# 3_0.net
KiCad netlist of a schematic drawn in Altium Designer
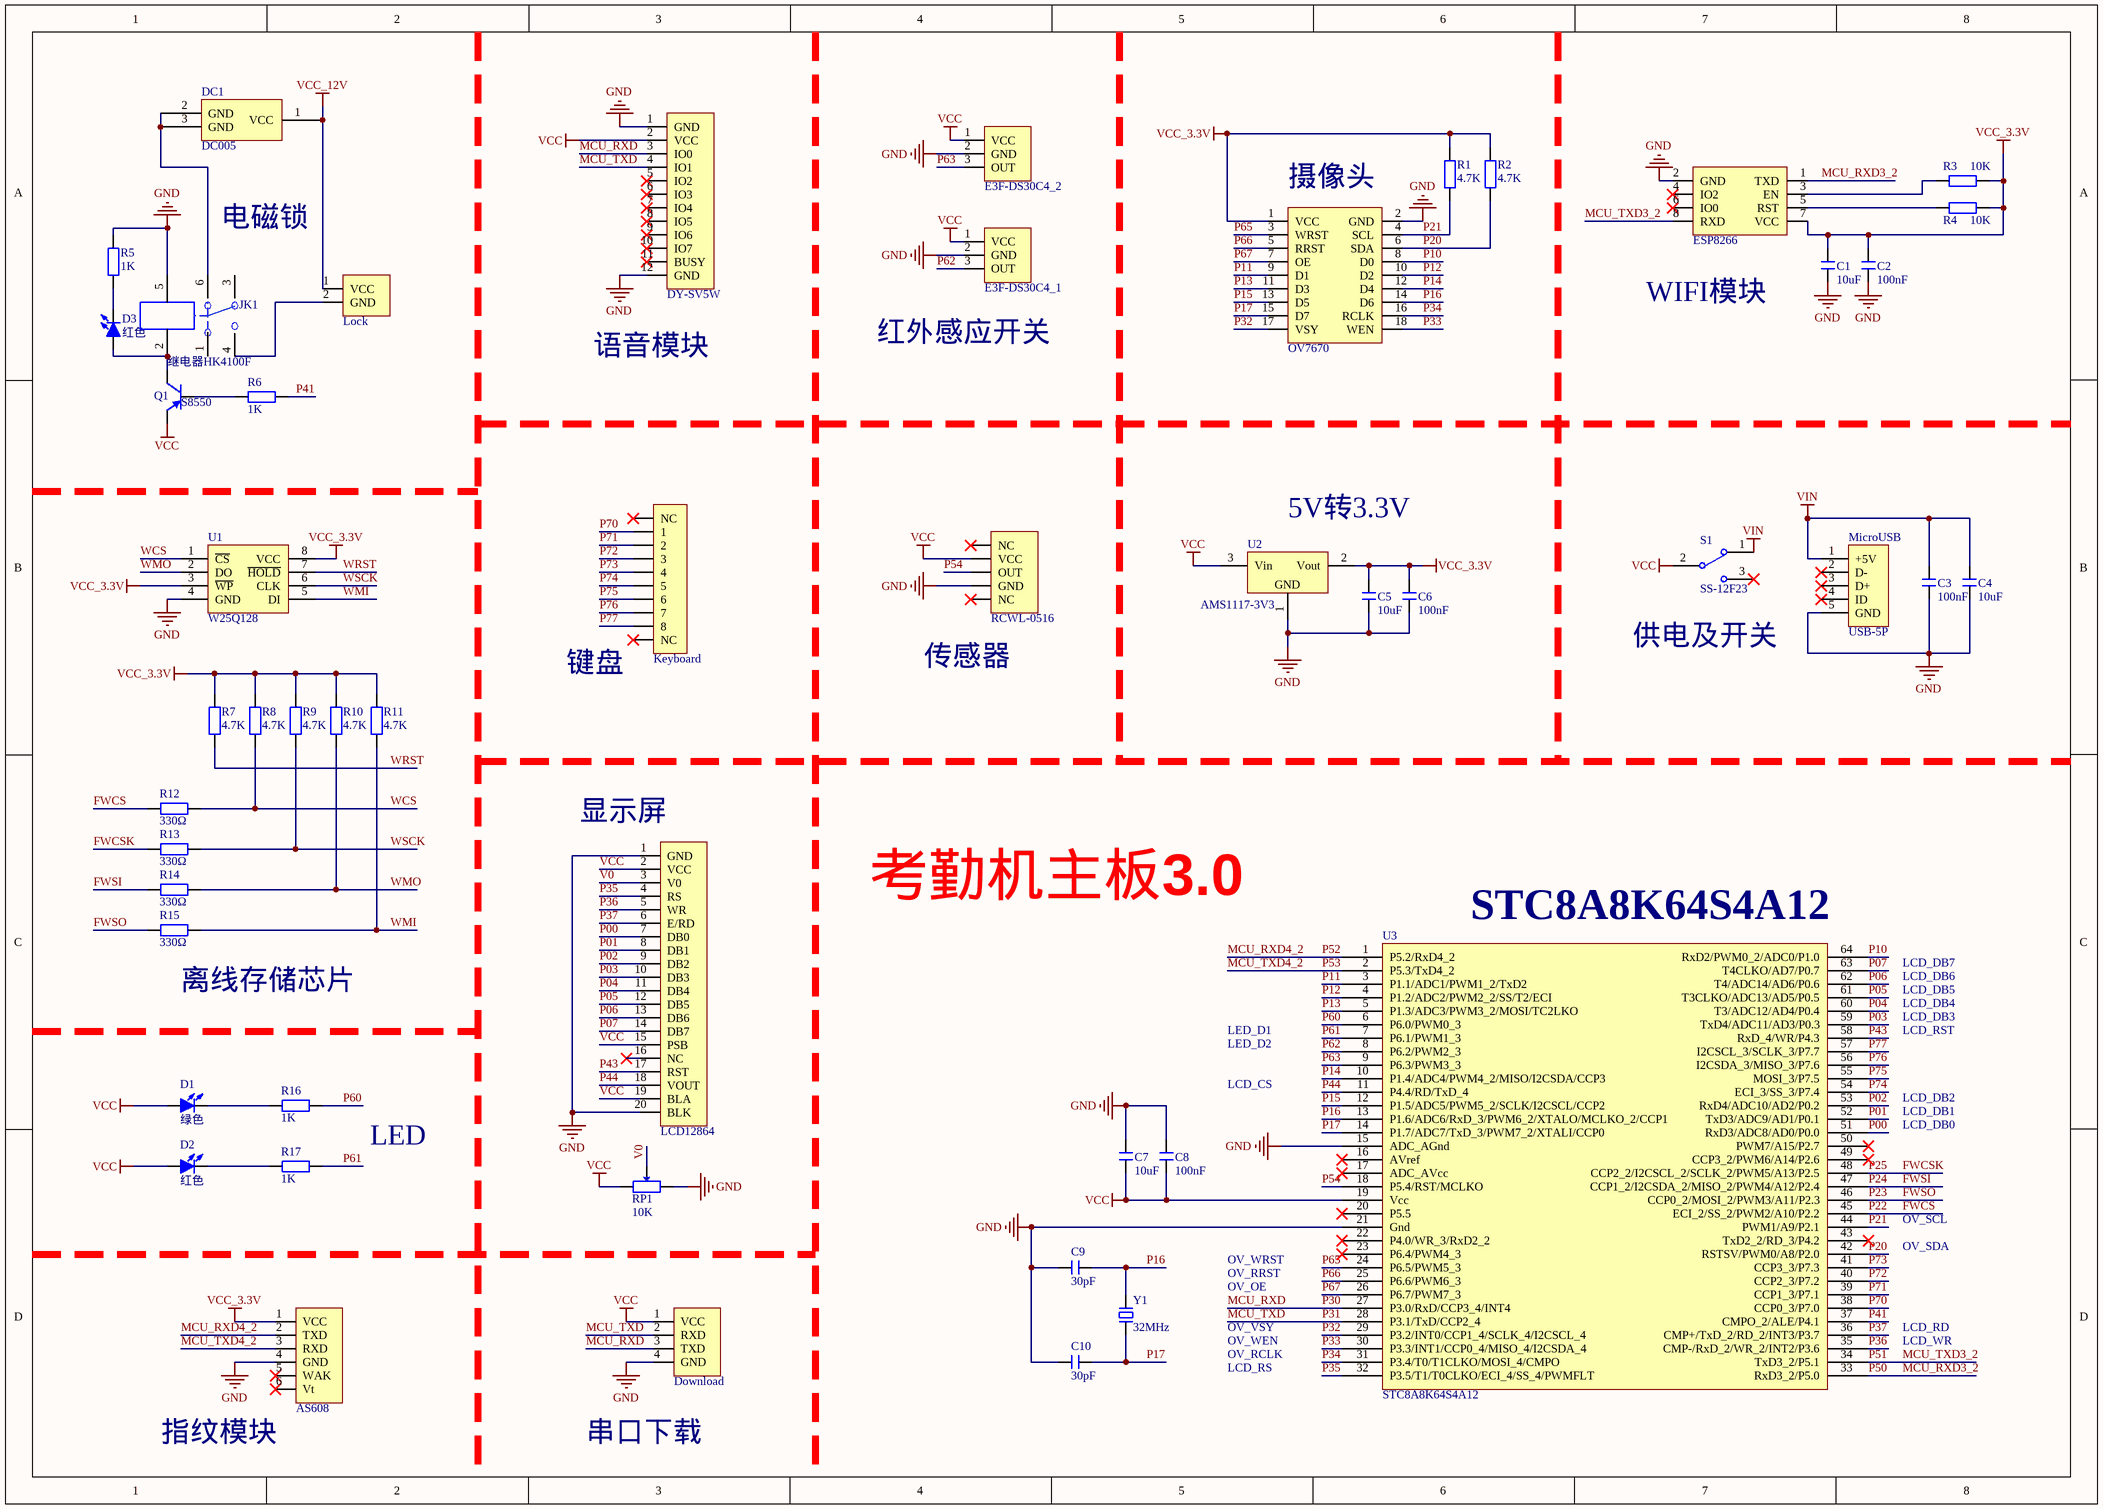
[diagram p0: 考勤机主板3.0.SchDoc]

(export (version "E")
  (design (tool "Eeschema 10.0.6"))
  (components
    (comp (ref "AS608")
      (value "HDR-1X6")
      (footprint "HDR2.54-LI-6P")
      (description "AS608")
      (fields (field (name "版权归属") "源创客"))
      (libsource (lib "考勤机主板3.0.") (part "指纹模块"))
    )
    (comp (ref "C1")
      (value "10uF")
      (footprint "C 0805_M")
      (description "无极性贴片电容")
      (fields (field (name "版权归属") "源创客"))
      (libsource (lib "考勤机主板3.0.") (part "C"))
    )
    (comp (ref "C2")
      (value "100nF")
      (footprint "C 0805_M")
      (description "无极性贴片电容")
      (fields (field (name "版权归属") "源创客"))
      (libsource (lib "考勤机主板3.0.") (part "C"))
    )
    (comp (ref "C3")
      (value "100nF")
      (footprint "C 0805_M")
      (description "无极性贴片电容")
      (fields (field (name "版权归属") "源创客"))
      (libsource (lib "考勤机主板3.0.") (part "C"))
    )
    (comp (ref "C4")
      (value "10uF")
      (footprint "C 0805_M")
      (description "无极性贴片电容")
      (fields (field (name "版权归属") "源创客"))
      (libsource (lib "考勤机主板3.0.") (part "C"))
    )
    (comp (ref "C5")
      (value "10uF")
      (footprint "C 0805_M")
      (description "无极性贴片电容")
      (fields (field (name "版权归属") "源创客"))
      (libsource (lib "考勤机主板3.0.") (part "C"))
    )
    (comp (ref "C6")
      (value "100nF")
      (footprint "C 0805_M")
      (description "无极性贴片电容")
      (fields (field (name "版权归属") "源创客"))
      (libsource (lib "考勤机主板3.0.") (part "C"))
    )
    (comp (ref "C7")
      (value "10uF")
      (footprint "C 0805_M")
      (description "无极性贴片电容")
      (fields (field (name "版权归属") "源创客"))
      (libsource (lib "考勤机主板3.0.") (part "C"))
    )
    (comp (ref "C8")
      (value "100nF")
      (footprint "C 0805_M")
      (description "无极性贴片电容")
      (fields (field (name "版权归属") "源创客"))
      (libsource (lib "考勤机主板3.0.") (part "C"))
    )
    (comp (ref "C9")
      (value "30pF")
      (footprint "C 0805_M")
      (description "无极性贴片电容")
      (fields (field (name "版权归属") "源创客"))
      (libsource (lib "考勤机主板3.0.") (part "C"))
    )
    (comp (ref "C10")
      (value "30pF")
      (footprint "C 0805_M")
      (description "无极性贴片电容")
      (fields (field (name "版权归属") "源创客"))
      (libsource (lib "考勤机主板3.0.") (part "C"))
    )
    (comp (ref "D1")
      (value "绿色")
      (footprint "LED 0805G")
      (description "贴片LED")
      (fields (field (name "版权归属") "源创客"))
      (libsource (lib "考勤机主板3.0.") (part "LED-SMD"))
    )
    (comp (ref "D2")
      (value "红色")
      (footprint "LED 0805R")
      (description "贴片LED")
      (fields (field (name "版权归属") "源创客"))
      (libsource (lib "考勤机主板3.0.") (part "LED-SMD"))
    )
    (comp (ref "D3")
      (value "红色")
      (footprint "LED 0805G")
      (description "贴片LED")
      (fields (field (name "版权归属") "源创客"))
      (libsource (lib "考勤机主板3.0.") (part "LED-SMD"))
    )
    (comp (ref "DC1") (value "DC005") (footprint "DC-005") (libsource (lib "考勤机主板3.0.") (part "DC005")))
    (comp (ref "Download")
      (value "HDR-1X4")
      (footprint "HDR2.54-LI-4P")
      (description "串口下载")
      (fields (field (name "版权归属") "源创客"))
      (libsource (lib "考勤机主板3.0.") (part "串口下载"))
    )
    (comp (ref "DY-SV5W")
      (value "HDR-1X12")
      (footprint "HDR2.54-M-LI-12P")
      (description "DY-SV5W")
      (fields (field (name "版权归属") "源创客"))
      (libsource (lib "考勤机主板3.0.") (part "语音模块"))
    )
    (comp (ref "E3F-DS30C4_1")
      (value "HDR-1X3")
      (footprint "HDR2.54-M-LI-3P")
      (description "E3F-DS30C4")
      (fields (field (name "版权归属") "源创客"))
      (libsource (lib "考勤机主板3.0.") (part "红外感应开关"))
    )
    (comp (ref "E3F-DS30C4_2")
      (value "HDR-1X3")
      (footprint "HDR2.54-M-LI-3P")
      (description "E3F-DS30C4")
      (fields (field (name "版权归属") "源创客"))
      (libsource (lib "考勤机主板3.0.") (part "红外感应开关"))
    )
    (comp (ref "ESP8266")
      (value "Header 4X2")
      (footprint "HDR2.54-LI-2x4P")
      (description "ESP8266-01")
      (fields (field (name "版权归属") "源创客"))
      (libsource (lib "考勤机主板3.0.") (part "WIFI模块"))
    )
    (comp (ref "JK1")
      (value "继电器HK4100F")
      (footprint "HK4100F - duplicate")
      (libsource (lib "元件库") (part "继电器HK4100F"))
    )
    (comp (ref "Keyboard")
      (value "HDR-1X10")
      (footprint "HDR2.54-M-LI-10P")
      (description "Keyboard")
      (fields (field (name "版权归属") "源创客"))
      (libsource (lib "考勤机主板3.0.") (part "键盘"))
    )
    (comp (ref "LCD12864")
      (value "HDR-1X20")
      (footprint "HDR2.54-M-LI-20P")
      (description "LCD12864")
      (fields (field (name "版权归属") "源创客"))
      (libsource (lib "考勤机主板3.0.") (part "显示屏"))
    )
    (comp (ref "Lock")
      (value "HDR-1X2")
      (footprint "XH2.54-WI-2P")
      (description "电磁锁")
      (fields (field (name "版权归属") "源创客"))
      (libsource (lib "考勤机主板3.0.") (part "电磁锁"))
    )
    (comp (ref "MicroUSB")
      (value "USB-5P")
      (footprint "USB")
      (description "MicroUSB")
      (fields (field (name "版权归属") "源创客"))
      (libsource (lib "考勤机主板3.0.") (part "MiceoUSB接口"))
    )
    (comp (ref "OV7670")
      (value "Header 9X2")
      (footprint "HDR2.54-LI-2x9P")
      (description "OV7670")
      (fields (field (name "版权归属") "源创客"))
      (libsource (lib "考勤机主板3.0.") (part "摄像头"))
    )
    (comp (ref "Q1")
      (value "S8550")
      (footprint "SOT23-3M")
      (description "高频放大-PNP型")
      (fields (field (name "版权归属") "源创客"))
      (libsource (lib "考勤机主板3.0.") (part "8550-SMD"))
    )
    (comp (ref "R1")
      (value "4.7K")
      (footprint "R 0805_M")
      (description "贴片电阻")
      (fields (field (name "版权归属") "源创客"))
      (libsource (lib "3.1   - 电阻-电容-电感") (part "R"))
    )
    (comp (ref "R2")
      (value "4.7K")
      (footprint "R 0805_M")
      (description "贴片电阻")
      (fields (field (name "版权归属") "源创客"))
      (libsource (lib "3.1   - 电阻-电容-电感") (part "R"))
    )
    (comp (ref "R3")
      (value "10K")
      (footprint "R 0805_M")
      (description "贴片电阻")
      (fields (field (name "版权归属") "源创客"))
      (libsource (lib "3.1   - 电阻-电容-电感") (part "R"))
    )
    (comp (ref "R4")
      (value "10K")
      (footprint "R 0805_M")
      (description "贴片电阻")
      (fields (field (name "版权归属") "源创客"))
      (libsource (lib "3.1   - 电阻-电容-电感") (part "R"))
    )
    (comp (ref "R5")
      (value "1K")
      (footprint "R 0805_M")
      (description "贴片电阻")
      (fields (field (name "版权归属") "源创客"))
      (libsource (lib "3.1   - 电阻-电容-电感") (part "R"))
    )
    (comp (ref "R6")
      (value "1K")
      (footprint "R 0805_M")
      (description "贴片电阻")
      (fields (field (name "版权归属") "源创客"))
      (libsource (lib "考勤机主板3.0.") (part "R"))
    )
    (comp (ref "R7")
      (value "4.7K")
      (footprint "R 0805_M")
      (description "贴片电阻")
      (fields (field (name "版权归属") "源创客"))
      (libsource (lib "考勤机主板3.0.") (part "R"))
    )
    (comp (ref "R8")
      (value "4.7K")
      (footprint "R 0805_M")
      (description "贴片电阻")
      (fields (field (name "版权归属") "源创客"))
      (libsource (lib "考勤机主板3.0.") (part "R"))
    )
    (comp (ref "R9")
      (value "4.7K")
      (footprint "R 0805_M")
      (description "贴片电阻")
      (fields (field (name "版权归属") "源创客"))
      (libsource (lib "考勤机主板3.0.") (part "R"))
    )
    (comp (ref "R10")
      (value "4.7K")
      (footprint "R 0805_M")
      (description "贴片电阻")
      (fields (field (name "版权归属") "源创客"))
      (libsource (lib "考勤机主板3.0.") (part "R"))
    )
    (comp (ref "R11")
      (value "4.7K")
      (footprint "R 0805_M")
      (description "贴片电阻")
      (fields (field (name "版权归属") "源创客"))
      (libsource (lib "考勤机主板3.0.") (part "R"))
    )
    (comp (ref "R12")
      (value "330Ω")
      (footprint "R 0805_M")
      (description "贴片电阻")
      (fields (field (name "版权归属") "源创客"))
      (libsource (lib "考勤机主板3.0.") (part "R"))
    )
    (comp (ref "R13")
      (value "330Ω")
      (footprint "R 0805_M")
      (description "贴片电阻")
      (fields (field (name "版权归属") "源创客"))
      (libsource (lib "考勤机主板3.0.") (part "R"))
    )
    (comp (ref "R14")
      (value "330Ω")
      (footprint "R 0805_M")
      (description "贴片电阻")
      (fields (field (name "版权归属") "源创客"))
      (libsource (lib "考勤机主板3.0.") (part "R"))
    )
    (comp (ref "R15")
      (value "330Ω")
      (footprint "R 0805_M")
      (description "贴片电阻")
      (fields (field (name "版权归属") "源创客"))
      (libsource (lib "考勤机主板3.0.") (part "R"))
    )
    (comp (ref "R16")
      (value "1K")
      (footprint "R 0805_M")
      (description "贴片电阻")
      (fields (field (name "版权归属") "源创客"))
      (libsource (lib "考勤机主板3.0.") (part "R"))
    )
    (comp (ref "R17")
      (value "1K")
      (footprint "R 0805_M")
      (description "贴片电阻")
      (fields (field (name "版权归属") "源创客"))
      (libsource (lib "考勤机主板3.0.") (part "R"))
    )
    (comp (ref "RCWL-0516")
      (value "HDR-1X5")
      (footprint "HDR2.54-M-LI-5P")
      (description "RCWL-0516")
      (fields (field (name "版权归属") "源创客"))
      (libsource (lib "考勤机主板3.0.") (part "传感器"))
    )
    (comp (ref "RP1")
      (value "10K")
      (footprint "RM065")
      (description "插件单联电位器")
      (fields (field (name "版权归属") "源创客"))
      (libsource (lib "3.1   - 电阻-电容-电感") (part "RP-ID"))
    )
    (comp (ref "S1")
      (value "SS-12F23")
      (footprint "SS-12F23")
      (description "1路波动开关")
      (fields (field (name "版权归属") "源创客"))
      (libsource (lib "考勤机主板3.0.") (part "SSW-1P"))
    )
    (comp (ref "U1")
      (value "W25Q128")
      (footprint "SOP8W_M")
      (description "离线存储芯片")
      (fields (field (name "版权归属") "源创客"))
      (libsource (lib "考勤机主板3.0.") (part "W25Q128"))
    )
    (comp (ref "U2")
      (value "AMS1117-3V3")
      (footprint "SOT-223")
      (description "三端稳压芯片")
      (fields (field (name "版权归属") "源创客"))
      (libsource (lib "考勤机主板3.0.") (part "AMS1117"))
    )
    (comp (ref "U3")
      (value "STC8A8K64S4A12")
      (footprint "LQFP-64")
      (description "IC")
      (libsource (lib "考勤机主板3.0.") (part "STC8A8K64S4A12"))
    )
    (comp (ref "Y1")
      (value "32MHz")
      (footprint "HC-49S")
      (description "2脚无源脚晶振")
      (fields (field (name "版权归属") "源创客"))
      (libsource (lib "考勤机主板3.0.") (part "XTAL-2P"))
    )
  )
  (nets
    (net (code "1") (name "/FWCS") (class "Default")
      (node (ref "R12") (pin "1") (pinfunction "1_1") (pintype "passive"))
      (node (ref "U3") (pin "45") (pinfunction "ECI_2/SS_2/PWM2/A10/P2.2_45") (pintype "passive"))
    )
    (net (code "2") (name "/FWCSK") (class "Default")
      (node (ref "R13") (pin "1") (pinfunction "1_1") (pintype "passive"))
      (node (ref "U3") (pin "48") (pinfunction "CCP2_2/I2CSCL_2/SCLK_2/PWM5/A13/P2.5_48") (pintype "passive"))
    )
    (net (code "3") (name "/FWSI") (class "Default")
      (node (ref "R14") (pin "1") (pinfunction "1_1") (pintype "passive"))
      (node (ref "U3") (pin "47") (pinfunction "CCP1_2/I2CSDA_2/MISO_2/PWM4/A12/P2.4_47") (pintype "passive"))
    )
    (net (code "4") (name "/FWSO") (class "Default")
      (node (ref "R15") (pin "1") (pinfunction "1_1") (pintype "passive"))
      (node (ref "U3") (pin "46") (pinfunction "CCP0_2/MOSI_2/PWM3/A11/P2.3_46") (pintype "passive"))
    )
    (net (code "5") (name "/MCU_RXD") (class "Default")
      (node (ref "DY-SV5W") (pin "3") (pinfunction "IO0_3") (pintype "passive"))
      (node (ref "Download") (pin "3") (pinfunction "TXD_3") (pintype "passive"))
      (node (ref "U3") (pin "27") (pinfunction "P3.0/RxD/CCP3_4/INT4_27") (pintype "passive"))
    )
    (net (code "6") (name "/MCU_RXD3_2") (class "Default")
      (node (ref "ESP8266") (pin "1") (pinfunction "TXD_1") (pintype "passive"))
      (node (ref "U3") (pin "33") (pinfunction "RxD3_2/P5.0_33") (pintype "passive"))
    )
    (net (code "7") (name "/MCU_RXD4_2") (class "Default")
      (node (ref "AS608") (pin "2") (pinfunction "TXD_2") (pintype "passive"))
      (node (ref "U3") (pin "1") (pinfunction "P5.2/RxD4_2_1") (pintype "passive"))
    )
    (net (code "8") (name "/MCU_TXD") (class "Default")
      (node (ref "DY-SV5W") (pin "4") (pinfunction "IO1_4") (pintype "passive"))
      (node (ref "Download") (pin "2") (pinfunction "RXD_2") (pintype "passive"))
      (node (ref "U3") (pin "28") (pinfunction "P3.1/TxD/CCP2_4_28") (pintype "passive"))
    )
    (net (code "9") (name "/MCU_TXD3_2") (class "Default")
      (node (ref "ESP8266") (pin "8") (pinfunction "RXD_8") (pintype "passive"))
      (node (ref "U3") (pin "34") (pinfunction "TxD3_2/P5.1_34") (pintype "passive"))
    )
    (net (code "10") (name "/MCU_TXD4_2") (class "Default")
      (node (ref "AS608") (pin "3") (pinfunction "RXD_3") (pintype "passive"))
      (node (ref "U3") (pin "2") (pinfunction "P5.3/TxD4_2_2") (pintype "passive"))
    )
    (net (code "11") (name "/P00") (class "Default")
      (node (ref "LCD12864") (pin "7") (pinfunction "DB0_7") (pintype "passive"))
      (node (ref "U3") (pin "51") (pinfunction "RxD3/ADC8/AD0/P0.0_51") (pintype "passive"))
    )
    (net (code "12") (name "/P01") (class "Default")
      (node (ref "LCD12864") (pin "8") (pinfunction "DB1_8") (pintype "passive"))
      (node (ref "U3") (pin "52") (pinfunction "TxD3/ADC9/AD1/P0.1_52") (pintype "passive"))
    )
    (net (code "13") (name "/P02") (class "Default")
      (node (ref "LCD12864") (pin "9") (pinfunction "DB2_9") (pintype "passive"))
      (node (ref "U3") (pin "53") (pinfunction "RxD4/ADC10/AD2/P0.2_53") (pintype "passive"))
    )
    (net (code "14") (name "/P03") (class "Default")
      (node (ref "LCD12864") (pin "10") (pinfunction "DB3_10") (pintype "passive"))
      (node (ref "U3") (pin "59") (pinfunction "TxD4/ADC11/AD3/P0.3_59") (pintype "passive"))
    )
    (net (code "15") (name "/P04") (class "Default")
      (node (ref "LCD12864") (pin "11") (pinfunction "DB4_11") (pintype "passive"))
      (node (ref "U3") (pin "60") (pinfunction "T3/ADC12/AD4/P0.4_60") (pintype "passive"))
    )
    (net (code "16") (name "/P05") (class "Default")
      (node (ref "LCD12864") (pin "12") (pinfunction "DB5_12") (pintype "passive"))
      (node (ref "U3") (pin "61") (pinfunction "T3CLKO/ADC13/AD5/P0.5_61") (pintype "passive"))
    )
    (net (code "17") (name "/P06") (class "Default")
      (node (ref "LCD12864") (pin "13") (pinfunction "DB6_13") (pintype "passive"))
      (node (ref "U3") (pin "62") (pinfunction "T4/ADC14/AD6/P0.6_62") (pintype "passive"))
    )
    (net (code "18") (name "/P07") (class "Default")
      (node (ref "LCD12864") (pin "14") (pinfunction "DB7_14") (pintype "passive"))
      (node (ref "U3") (pin "63") (pinfunction "T4CLKO/AD7/P0.7_63") (pintype "passive"))
    )
    (net (code "19") (name "/P10") (class "Default")
      (node (ref "OV7670") (pin "8") (pinfunction "D0_8") (pintype "passive"))
      (node (ref "U3") (pin "64") (pinfunction "RxD2/PWM0_2/ADC0/P1.0_64") (pintype "passive"))
    )
    (net (code "20") (name "/P11") (class "Default")
      (node (ref "OV7670") (pin "9") (pinfunction "D1_9") (pintype "passive"))
      (node (ref "U3") (pin "3") (pinfunction "P1.1/ADC1/PWM1_2/TxD2_3") (pintype "passive"))
    )
    (net (code "21") (name "/P12") (class "Default")
      (node (ref "OV7670") (pin "10") (pinfunction "D2_10") (pintype "passive"))
      (node (ref "U3") (pin "4") (pinfunction "P1.2/ADC2/PWM2_2/SS/T2/ECI_4") (pintype "passive"))
    )
    (net (code "22") (name "/P13") (class "Default")
      (node (ref "OV7670") (pin "11") (pinfunction "D3_11") (pintype "passive"))
      (node (ref "U3") (pin "5") (pinfunction "P1.3/ADC3/PWM3_2/MOSI/TC2LKO_5") (pintype "passive"))
    )
    (net (code "23") (name "/P14") (class "Default")
      (node (ref "OV7670") (pin "12") (pinfunction "D4_12") (pintype "passive"))
      (node (ref "U3") (pin "10") (pinfunction "P1.4/ADC4/PWM4_2/MISO/I2CSDA/CCP3_10") (pintype "passive"))
    )
    (net (code "24") (name "/P15") (class "Default")
      (node (ref "OV7670") (pin "13") (pinfunction "D5_13") (pintype "passive"))
      (node (ref "U3") (pin "12") (pinfunction "P1.5/ADC5/PWM5_2/SCLK/I2CSCL/CCP2_12") (pintype "passive"))
    )
    (net (code "25") (name "/P16") (class "Default")
      (node (ref "C9") (pin "2") (pinfunction "2_2") (pintype "passive"))
      (node (ref "OV7670") (pin "14") (pinfunction "D6_14") (pintype "passive"))
      (node (ref "U3") (pin "13") (pinfunction "P1.6/ADC6/RxD_3/PWM6_2/XTALO/MCLKO_2/CCP1_13") (pintype "passive"))
      (node (ref "Y1") (pin "2") (pinfunction "2_2") (pintype "passive"))
    )
    (net (code "26") (name "/P17") (class "Default")
      (node (ref "C10") (pin "2") (pinfunction "2_2") (pintype "passive"))
      (node (ref "OV7670") (pin "15") (pinfunction "D7_15") (pintype "passive"))
      (node (ref "U3") (pin "14") (pinfunction "P1.7/ADC7/TxD_3/PWM7_2/XTALI/CCP0_14") (pintype "passive"))
      (node (ref "Y1") (pin "1") (pinfunction "1_1") (pintype "passive"))
    )
    (net (code "27") (name "/P20") (class "Default")
      (node (ref "OV7670") (pin "6") (pinfunction "SDA_6") (pintype "passive"))
      (node (ref "R2") (pin "1") (pinfunction "1_1") (pintype "passive"))
      (node (ref "U3") (pin "42") (pinfunction "RSTSV/PWM0/A8/P2.0_42") (pintype "passive"))
    )
    (net (code "28") (name "/P21") (class "Default")
      (node (ref "OV7670") (pin "4") (pinfunction "SCL_4") (pintype "passive"))
      (node (ref "R1") (pin "1") (pinfunction "1_1") (pintype "passive"))
      (node (ref "U3") (pin "44") (pinfunction "PWM1/A9/P2.1_44") (pintype "passive"))
    )
    (net (code "29") (name "/P32") (class "Default")
      (node (ref "OV7670") (pin "17") (pinfunction "VSY_17") (pintype "passive"))
      (node (ref "U3") (pin "29") (pinfunction "P3.2/INT0/CCP1_4/SCLK_4/I2CSCL_4_29") (pintype "passive"))
    )
    (net (code "30") (name "/P33") (class "Default")
      (node (ref "OV7670") (pin "18") (pinfunction "WEN_18") (pintype "passive"))
      (node (ref "U3") (pin "30") (pinfunction "P3.3/INT1/CCP0_4/MISO_4/I2CSDA_4_30") (pintype "passive"))
    )
    (net (code "31") (name "/P34") (class "Default")
      (node (ref "OV7670") (pin "16") (pinfunction "RCLK_16") (pintype "passive"))
      (node (ref "U3") (pin "31") (pinfunction "P3.4/T0/T1CLKO/MOSI_4/CMPO_31") (pintype "passive"))
    )
    (net (code "32") (name "/P35") (class "Default")
      (node (ref "LCD12864") (pin "4") (pinfunction "RS_4") (pintype "passive"))
      (node (ref "U3") (pin "32") (pinfunction "P3.5/T1/T0CLKO/ECI_4/SS_4/PWMFLT_32") (pintype "passive"))
    )
    (net (code "33") (name "/P36") (class "Default")
      (node (ref "LCD12864") (pin "5") (pinfunction "WR_5") (pintype "passive"))
      (node (ref "U3") (pin "35") (pinfunction "CMP-/RxD_2/WR_2/INT2/P3.6_35") (pintype "passive"))
    )
    (net (code "34") (name "/P37") (class "Default")
      (node (ref "LCD12864") (pin "6") (pinfunction "E/RD_6") (pintype "passive"))
      (node (ref "U3") (pin "36") (pinfunction "CMP+/TxD_2/RD_2/INT3/P3.7_36") (pintype "passive"))
    )
    (net (code "35") (name "/P41") (class "Default")
      (node (ref "R6") (pin "2") (pinfunction "2_2") (pintype "passive"))
      (node (ref "U3") (pin "37") (pinfunction "CMPO_2/ALE/P4.1_37") (pintype "passive"))
    )
    (net (code "36") (name "/P43") (class "Default")
      (node (ref "LCD12864") (pin "17") (pinfunction "RST_17") (pintype "passive"))
      (node (ref "U3") (pin "58") (pinfunction "RxD_4/WR/P4.3_58") (pintype "passive"))
    )
    (net (code "37") (name "/P44") (class "Default")
      (node (ref "LCD12864") (pin "18") (pinfunction "VOUT_18") (pintype "passive"))
      (node (ref "U3") (pin "11") (pinfunction "P4.4/RD/TxD_4_11") (pintype "passive"))
    )
    (net (code "38") (name "/P54") (class "Default")
      (node (ref "RCWL-0516") (pin "3") (pinfunction "OUT_3") (pintype "passive"))
      (node (ref "U3") (pin "18") (pinfunction "P5.4/RST/MCLKO_18") (pintype "passive"))
    )
    (net (code "39") (name "/P60") (class "Default")
      (node (ref "R16") (pin "2") (pinfunction "2_2") (pintype "passive"))
      (node (ref "U3") (pin "6") (pinfunction "P6.0/PWM0_3_6") (pintype "passive"))
    )
    (net (code "40") (name "/P61") (class "Default")
      (node (ref "R17") (pin "2") (pinfunction "2_2") (pintype "passive"))
      (node (ref "U3") (pin "7") (pinfunction "P6.1/PWM1_3_7") (pintype "passive"))
    )
    (net (code "41") (name "/P62") (class "Default")
      (node (ref "E3F-DS30C4_1") (pin "3") (pinfunction "OUT_3") (pintype "passive"))
      (node (ref "U3") (pin "8") (pinfunction "P6.2/PWM2_3_8") (pintype "passive"))
    )
    (net (code "42") (name "/P63") (class "Default")
      (node (ref "E3F-DS30C4_2") (pin "3") (pinfunction "OUT_3") (pintype "passive"))
      (node (ref "U3") (pin "9") (pinfunction "P6.3/PWM3_3_9") (pintype "passive"))
    )
    (net (code "43") (name "/P65") (class "Default")
      (node (ref "OV7670") (pin "3") (pinfunction "WRST_3") (pintype "passive"))
      (node (ref "U3") (pin "24") (pinfunction "P6.5/PWM5_3_24") (pintype "passive"))
    )
    (net (code "44") (name "/P66") (class "Default")
      (node (ref "OV7670") (pin "5") (pinfunction "RRST_5") (pintype "passive"))
      (node (ref "U3") (pin "25") (pinfunction "P6.6/PWM6_3_25") (pintype "passive"))
    )
    (net (code "45") (name "/P67") (class "Default")
      (node (ref "OV7670") (pin "7") (pinfunction "OE_7") (pintype "passive"))
      (node (ref "U3") (pin "26") (pinfunction "P6.7/PWM7_3_26") (pintype "passive"))
    )
    (net (code "46") (name "/P70") (class "Default")
      (node (ref "Keyboard") (pin "2") (pinfunction "1_2") (pintype "passive"))
      (node (ref "U3") (pin "38") (pinfunction "CCP0_3/P7.0_38") (pintype "passive"))
    )
    (net (code "47") (name "/P71") (class "Default")
      (node (ref "Keyboard") (pin "3") (pinfunction "2_3") (pintype "passive"))
      (node (ref "U3") (pin "39") (pinfunction "CCP1_3/P7.1_39") (pintype "passive"))
    )
    (net (code "48") (name "/P72") (class "Default")
      (node (ref "Keyboard") (pin "4") (pinfunction "3_4") (pintype "passive"))
      (node (ref "U3") (pin "40") (pinfunction "CCP2_3/P7.2_40") (pintype "passive"))
    )
    (net (code "49") (name "/P73") (class "Default")
      (node (ref "Keyboard") (pin "5") (pinfunction "4_5") (pintype "passive"))
      (node (ref "U3") (pin "41") (pinfunction "CCP3_3/P7.3_41") (pintype "passive"))
    )
    (net (code "50") (name "/P74") (class "Default")
      (node (ref "Keyboard") (pin "6") (pinfunction "5_6") (pintype "passive"))
      (node (ref "U3") (pin "54") (pinfunction "ECI_3/SS_3/P7.4_54") (pintype "passive"))
    )
    (net (code "51") (name "/P75") (class "Default")
      (node (ref "Keyboard") (pin "7") (pinfunction "6_7") (pintype "passive"))
      (node (ref "U3") (pin "55") (pinfunction "MOSI_3/P7.5_55") (pintype "passive"))
    )
    (net (code "52") (name "/P76") (class "Default")
      (node (ref "Keyboard") (pin "8") (pinfunction "7_8") (pintype "passive"))
      (node (ref "U3") (pin "56") (pinfunction "I2CSDA_3/MISO_3/P7.6_56") (pintype "passive"))
    )
    (net (code "53") (name "/P77") (class "Default")
      (node (ref "Keyboard") (pin "9") (pinfunction "8_9") (pintype "passive"))
      (node (ref "U3") (pin "57") (pinfunction "I2CSCL_3/SCLK_3/P7.7_57") (pintype "passive"))
    )
    (net (code "54") (name "/V0") (class "Default")
      (node (ref "LCD12864") (pin "3") (pinfunction "V0_3") (pintype "passive"))
      (node (ref "RP1") (pin "2") (pinfunction "2_2") (pintype "passive"))
    )
    (net (code "55") (name "/WCS") (class "Default")
      (node (ref "R12") (pin "2") (pinfunction "2_2") (pintype "passive"))
      (node (ref "R8") (pin "1") (pinfunction "1_1") (pintype "passive"))
      (node (ref "U1") (pin "1") (pinfunction "~{CS}_1") (pintype "passive"))
    )
    (net (code "56") (name "/WMI") (class "Default")
      (node (ref "R11") (pin "1") (pinfunction "1_1") (pintype "passive"))
      (node (ref "R15") (pin "2") (pinfunction "2_2") (pintype "passive"))
      (node (ref "U1") (pin "5") (pinfunction "DI_5") (pintype "passive"))
    )
    (net (code "57") (name "/WMO") (class "Default")
      (node (ref "R10") (pin "1") (pinfunction "1_1") (pintype "passive"))
      (node (ref "R14") (pin "2") (pinfunction "2_2") (pintype "passive"))
      (node (ref "U1") (pin "2") (pinfunction "DO_2") (pintype "passive"))
    )
    (net (code "58") (name "/WRST") (class "Default")
      (node (ref "R7") (pin "1") (pinfunction "1_1") (pintype "passive"))
      (node (ref "U1") (pin "7") (pinfunction "~{HOLD}_7") (pintype "passive"))
    )
    (net (code "59") (name "/WSCK") (class "Default")
      (node (ref "R13") (pin "2") (pinfunction "2_2") (pintype "passive"))
      (node (ref "R9") (pin "1") (pinfunction "1_1") (pintype "passive"))
      (node (ref "U1") (pin "6") (pinfunction "CLK_6") (pintype "passive"))
    )
    (net (code "60") (name "GND") (class "Default")
      (node (ref "AS608") (pin "4") (pinfunction "GND_4") (pintype "passive"))
      (node (ref "C1") (pin "1") (pinfunction "1_1") (pintype "passive"))
      (node (ref "C10") (pin "1") (pinfunction "1_1") (pintype "passive"))
      (node (ref "C2") (pin "1") (pinfunction "1_1") (pintype "passive"))
      (node (ref "C3") (pin "1") (pinfunction "1_1") (pintype "passive"))
      (node (ref "C4") (pin "1") (pinfunction "1_1") (pintype "passive"))
      (node (ref "C5") (pin "1") (pinfunction "1_1") (pintype "passive"))
      (node (ref "C6") (pin "1") (pinfunction "1_1") (pintype "passive"))
      (node (ref "C7") (pin "2") (pinfunction "2_2") (pintype "passive"))
      (node (ref "C8") (pin "2") (pinfunction "2_2") (pintype "passive"))
      (node (ref "C9") (pin "1") (pinfunction "1_1") (pintype "passive"))
      (node (ref "DY-SV5W") (pin "1") (pinfunction "GND_1") (pintype "passive"))
      (node (ref "DY-SV5W") (pin "12") (pinfunction "GND_12") (pintype "passive"))
      (node (ref "Download") (pin "4") (pinfunction "GND_4") (pintype "passive"))
      (node (ref "E3F-DS30C4_1") (pin "2") (pinfunction "GND_2") (pintype "passive"))
      (node (ref "E3F-DS30C4_2") (pin "2") (pinfunction "GND_2") (pintype "passive"))
      (node (ref "ESP8266") (pin "2") (pinfunction "GND_2") (pintype "passive"))
      (node (ref "JK1") (pin "5") (pinfunction "5_5") (pintype "passive"))
      (node (ref "LCD12864") (pin "1") (pinfunction "GND_1") (pintype "passive"))
      (node (ref "LCD12864") (pin "20") (pinfunction "BLK_20") (pintype "passive"))
      (node (ref "MicroUSB") (pin "5") (pinfunction "GND_5") (pintype "passive"))
      (node (ref "OV7670") (pin "2") (pinfunction "GND_2") (pintype "passive"))
      (node (ref "R5") (pin "2") (pinfunction "2_2") (pintype "passive"))
      (node (ref "RCWL-0516") (pin "4") (pinfunction "GND_4") (pintype "passive"))
      (node (ref "RP1") (pin "3") (pinfunction "3_3") (pintype "passive"))
      (node (ref "U1") (pin "4") (pinfunction "GND_4") (pintype "passive"))
      (node (ref "U2") (pin "1") (pinfunction "GND_1") (pintype "passive"))
      (node (ref "U3") (pin "15") (pinfunction "ADC_AGnd_15") (pintype "passive"))
      (node (ref "U3") (pin "21") (pinfunction "Gnd_21") (pintype "passive"))
    )
    (net (code "61") (name "Net-(D1-K)") (class "Default")
      (node (ref "D1") (pin "2") (pinfunction "K_2") (pintype "passive"))
      (node (ref "R16") (pin "1") (pinfunction "1_1") (pintype "passive"))
    )
    (net (code "62") (name "Net-(D2-K)") (class "Default")
      (node (ref "D2") (pin "2") (pinfunction "K_2") (pintype "passive"))
      (node (ref "R17") (pin "1") (pinfunction "1_1") (pintype "passive"))
    )
    (net (code "63") (name "Net-(D3-A)") (class "Default")
      (node (ref "D3") (pin "1") (pinfunction "A_1") (pintype "passive"))
      (node (ref "JK1") (pin "2") (pinfunction "2_2") (pintype "passive"))
      (node (ref "Q1") (pin "3") (pinfunction "C_3") (pintype "passive"))
    )
    (net (code "64") (name "Net-(D3-K)") (class "Default")
      (node (ref "D3") (pin "2") (pinfunction "K_2") (pintype "passive"))
      (node (ref "R5") (pin "1") (pinfunction "1_1") (pintype "passive"))
    )
    (net (code "65") (name "Net-(DC1-GND-Pad2)") (class "Default")
      (node (ref "DC1") (pin "2") (pinfunction "GND_2") (pintype "passive"))
      (node (ref "DC1") (pin "3") (pinfunction "GND_3") (pintype "passive"))
      (node (ref "JK1") (pin "6") (pinfunction "6_6") (pintype "passive"))
    )
    (net (code "66") (name "Net-(ESP8266-EN)") (class "Default")
      (node (ref "ESP8266") (pin "3") (pinfunction "EN_3") (pintype "passive"))
      (node (ref "R3") (pin "1") (pinfunction "1_1") (pintype "passive"))
    )
    (net (code "67") (name "Net-(ESP8266-RST)") (class "Default")
      (node (ref "ESP8266") (pin "5") (pinfunction "RST_5") (pintype "passive"))
      (node (ref "R4") (pin "1") (pinfunction "1_1") (pintype "passive"))
    )
    (net (code "68") (name "Net-(Lock-GND)") (class "Default")
      (node (ref "JK1") (pin "4") (pinfunction "4_4") (pintype "passive"))
      (node (ref "Lock") (pin "2") (pinfunction "GND_2") (pintype "passive"))
    )
    (net (code "69") (name "Net-(Q1-B)") (class "Default")
      (node (ref "Q1") (pin "1") (pinfunction "B_1") (pintype "passive"))
      (node (ref "R6") (pin "1") (pinfunction "1_1") (pintype "passive"))
    )
    (net (code "70") (name "VCC") (class "Default")
      (node (ref "C7") (pin "1") (pinfunction "1_1") (pintype "passive"))
      (node (ref "C8") (pin "1") (pinfunction "1_1") (pintype "passive"))
      (node (ref "D1") (pin "1") (pinfunction "A_1") (pintype "passive"))
      (node (ref "D2") (pin "1") (pinfunction "A_1") (pintype "passive"))
      (node (ref "DY-SV5W") (pin "2") (pinfunction "VCC_2") (pintype "passive"))
      (node (ref "Download") (pin "1") (pinfunction "VCC_1") (pintype "passive"))
      (node (ref "E3F-DS30C4_1") (pin "1") (pinfunction "VCC_1") (pintype "passive"))
      (node (ref "E3F-DS30C4_2") (pin "1") (pinfunction "VCC_1") (pintype "passive"))
      (node (ref "LCD12864") (pin "15") (pinfunction "PSB_15") (pintype "passive"))
      (node (ref "LCD12864") (pin "19") (pinfunction "BLA_19") (pintype "passive"))
      (node (ref "LCD12864") (pin "2") (pinfunction "VCC_2") (pintype "passive"))
      (node (ref "Q1") (pin "2") (pinfunction "E_2") (pintype "passive"))
      (node (ref "RCWL-0516") (pin "2") (pinfunction "VCC_2") (pintype "passive"))
      (node (ref "RP1") (pin "1") (pinfunction "1_1") (pintype "passive"))
      (node (ref "S1") (pin "2") (pinfunction "2_2") (pintype "passive"))
      (node (ref "U2") (pin "3") (pinfunction "Vin_3") (pintype "passive"))
      (node (ref "U3") (pin "19") (pinfunction "Vcc_19") (pintype "passive"))
    )
    (net (code "71") (name "VCC_3.3V") (class "Default")
      (node (ref "AS608") (pin "1") (pinfunction "VCC_1") (pintype "passive"))
      (node (ref "C1") (pin "2") (pinfunction "2_2") (pintype "passive"))
      (node (ref "C2") (pin "2") (pinfunction "2_2") (pintype "passive"))
      (node (ref "C5") (pin "2") (pinfunction "2_2") (pintype "passive"))
      (node (ref "C6") (pin "2") (pinfunction "2_2") (pintype "passive"))
      (node (ref "ESP8266") (pin "7") (pinfunction "VCC_7") (pintype "passive"))
      (node (ref "OV7670") (pin "1") (pinfunction "VCC_1") (pintype "passive"))
      (node (ref "R1") (pin "2") (pinfunction "2_2") (pintype "passive"))
      (node (ref "R10") (pin "2") (pinfunction "2_2") (pintype "passive"))
      (node (ref "R11") (pin "2") (pinfunction "2_2") (pintype "passive"))
      (node (ref "R2") (pin "2") (pinfunction "2_2") (pintype "passive"))
      (node (ref "R3") (pin "2") (pinfunction "2_2") (pintype "passive"))
      (node (ref "R4") (pin "2") (pinfunction "2_2") (pintype "passive"))
      (node (ref "R7") (pin "2") (pinfunction "2_2") (pintype "passive"))
      (node (ref "R8") (pin "2") (pinfunction "2_2") (pintype "passive"))
      (node (ref "R9") (pin "2") (pinfunction "2_2") (pintype "passive"))
      (node (ref "U1") (pin "3") (pinfunction "~{WP}_3") (pintype "passive"))
      (node (ref "U1") (pin "8") (pinfunction "VCC_8") (pintype "passive"))
      (node (ref "U2") (pin "2") (pinfunction "Vout_2") (pintype "passive"))
    )
    (net (code "72") (name "VCC_12V") (class "Default")
      (node (ref "DC1") (pin "1") (pinfunction "VCC_1") (pintype "passive"))
      (node (ref "Lock") (pin "1") (pinfunction "VCC_1") (pintype "passive"))
    )
    (net (code "73") (name "VIN") (class "Default")
      (node (ref "C3") (pin "2") (pinfunction "2_2") (pintype "passive"))
      (node (ref "C4") (pin "2") (pinfunction "2_2") (pintype "passive"))
      (node (ref "MicroUSB") (pin "1") (pinfunction "+5V_1") (pintype "passive"))
      (node (ref "S1") (pin "1") (pinfunction "1_1") (pintype "passive"))
    )
    (net (code "74") (name "unconnected-(AS608-Vt-Pad6)") (class "Default")
      (node (ref "AS608") (pin "6") (pinfunction "Vt_6") (pintype "passive+no_connect"))
    )
    (net (code "75") (name "unconnected-(AS608-WAK-Pad5)") (class "Default")
      (node (ref "AS608") (pin "5") (pinfunction "WAK_5") (pintype "passive+no_connect"))
    )
    (net (code "76") (name "unconnected-(DY-SV5W-BUSY-Pad11)") (class "Default")
      (node (ref "DY-SV5W") (pin "11") (pinfunction "BUSY_11") (pintype "passive+no_connect"))
    )
    (net (code "77") (name "unconnected-(DY-SV5W-IO2-Pad5)") (class "Default")
      (node (ref "DY-SV5W") (pin "5") (pinfunction "IO2_5") (pintype "passive+no_connect"))
    )
    (net (code "78") (name "unconnected-(DY-SV5W-IO3-Pad6)") (class "Default")
      (node (ref "DY-SV5W") (pin "6") (pinfunction "IO3_6") (pintype "passive+no_connect"))
    )
    (net (code "79") (name "unconnected-(DY-SV5W-IO4-Pad7)") (class "Default")
      (node (ref "DY-SV5W") (pin "7") (pinfunction "IO4_7") (pintype "passive+no_connect"))
    )
    (net (code "80") (name "unconnected-(DY-SV5W-IO5-Pad8)") (class "Default")
      (node (ref "DY-SV5W") (pin "8") (pinfunction "IO5_8") (pintype "passive+no_connect"))
    )
    (net (code "81") (name "unconnected-(DY-SV5W-IO6-Pad9)") (class "Default")
      (node (ref "DY-SV5W") (pin "9") (pinfunction "IO6_9") (pintype "passive+no_connect"))
    )
    (net (code "82") (name "unconnected-(DY-SV5W-IO7-Pad10)") (class "Default")
      (node (ref "DY-SV5W") (pin "10") (pinfunction "IO7_10") (pintype "passive+no_connect"))
    )
    (net (code "83") (name "unconnected-(ESP8266-IO0-Pad6)") (class "Default")
      (node (ref "ESP8266") (pin "6") (pinfunction "IO0_6") (pintype "passive+no_connect"))
    )
    (net (code "84") (name "unconnected-(ESP8266-IO2-Pad4)") (class "Default")
      (node (ref "ESP8266") (pin "4") (pinfunction "IO2_4") (pintype "passive+no_connect"))
    )
    (net (code "85") (name "unconnected-(JK1-Pad1)") (class "Default")
      (node (ref "JK1") (pin "1") (pinfunction "1_1") (pintype "passive"))
    )
    (net (code "86") (name "unconnected-(JK1-Pad3)") (class "Default")
      (node (ref "JK1") (pin "3") (pinfunction "3_3") (pintype "passive"))
    )
    (net (code "87") (name "unconnected-(Keyboard-NC-Pad1)") (class "Default")
      (node (ref "Keyboard") (pin "1") (pinfunction "NC_1") (pintype "passive+no_connect"))
    )
    (net (code "88") (name "unconnected-(Keyboard-NC-Pad10)") (class "Default")
      (node (ref "Keyboard") (pin "10") (pinfunction "NC_10") (pintype "passive+no_connect"))
    )
    (net (code "89") (name "unconnected-(LCD12864-NC-Pad16)") (class "Default")
      (node (ref "LCD12864") (pin "16") (pinfunction "NC_16") (pintype "passive+no_connect"))
    )
    (net (code "90") (name "unconnected-(MicroUSB-D+-Pad3)") (class "Default")
      (node (ref "MicroUSB") (pin "3") (pinfunction "D+_3") (pintype "passive+no_connect"))
    )
    (net (code "91") (name "unconnected-(MicroUSB-D--Pad2)") (class "Default")
      (node (ref "MicroUSB") (pin "2") (pinfunction "D-_2") (pintype "passive+no_connect"))
    )
    (net (code "92") (name "unconnected-(MicroUSB-ID-Pad4)") (class "Default")
      (node (ref "MicroUSB") (pin "4") (pinfunction "ID_4") (pintype "passive+no_connect"))
    )
    (net (code "93") (name "unconnected-(RCWL-0516-NC-Pad1)") (class "Default")
      (node (ref "RCWL-0516") (pin "1") (pinfunction "NC_1") (pintype "passive+no_connect"))
    )
    (net (code "94") (name "unconnected-(RCWL-0516-NC-Pad5)") (class "Default")
      (node (ref "RCWL-0516") (pin "5") (pinfunction "NC_5") (pintype "passive+no_connect"))
    )
    (net (code "95") (name "unconnected-(S1-Pad3)") (class "Default")
      (node (ref "S1") (pin "3") (pinfunction "3_3") (pintype "passive+no_connect"))
    )
    (net (code "96") (name "unconnected-(U3-ADC_AVcc-Pad17)") (class "Default")
      (node (ref "U3") (pin "17") (pinfunction "ADC_AVcc_17") (pintype "passive+no_connect"))
    )
    (net (code "97") (name "unconnected-(U3-AVref-Pad16)") (class "Default")
      (node (ref "U3") (pin "16") (pinfunction "AVref_16") (pintype "passive+no_connect"))
    )
    (net (code "98") (name "unconnected-(U3-CCP3_2{slash}PWM6{slash}A14{slash}P2.6-Pad49)") (class "Default")
      (node (ref "U3") (pin "49") (pinfunction "CCP3_2/PWM6/A14/P2.6_49") (pintype "passive+no_connect"))
    )
    (net (code "99") (name "unconnected-(U3-P4.0{slash}WR_3{slash}RxD2_2-Pad22)") (class "Default")
      (node (ref "U3") (pin "22") (pinfunction "P4.0/WR_3/RxD2_2_22") (pintype "passive+no_connect"))
    )
    (net (code "100") (name "unconnected-(U3-P5.5-Pad20)") (class "Default")
      (node (ref "U3") (pin "20") (pinfunction "P5.5_20") (pintype "passive+no_connect"))
    )
    (net (code "101") (name "unconnected-(U3-P6.4{slash}PWM4_3-Pad23)") (class "Default")
      (node (ref "U3") (pin "23") (pinfunction "P6.4/PWM4_3_23") (pintype "passive+no_connect"))
    )
    (net (code "102") (name "unconnected-(U3-PWM7{slash}A15{slash}P2.7-Pad50)") (class "Default")
      (node (ref "U3") (pin "50") (pinfunction "PWM7/A15/P2.7_50") (pintype "passive+no_connect"))
    )
    (net (code "103") (name "unconnected-(U3-TxD2_2{slash}RD_3{slash}P4.2-Pad43)") (class "Default")
      (node (ref "U3") (pin "43") (pinfunction "TxD2_2/RD_3/P4.2_43") (pintype "passive+no_connect"))
    )
  )
)
